# 2019SpaceAppsTrophy.net
KiCad netlist of a schematic drawn in EAGLE
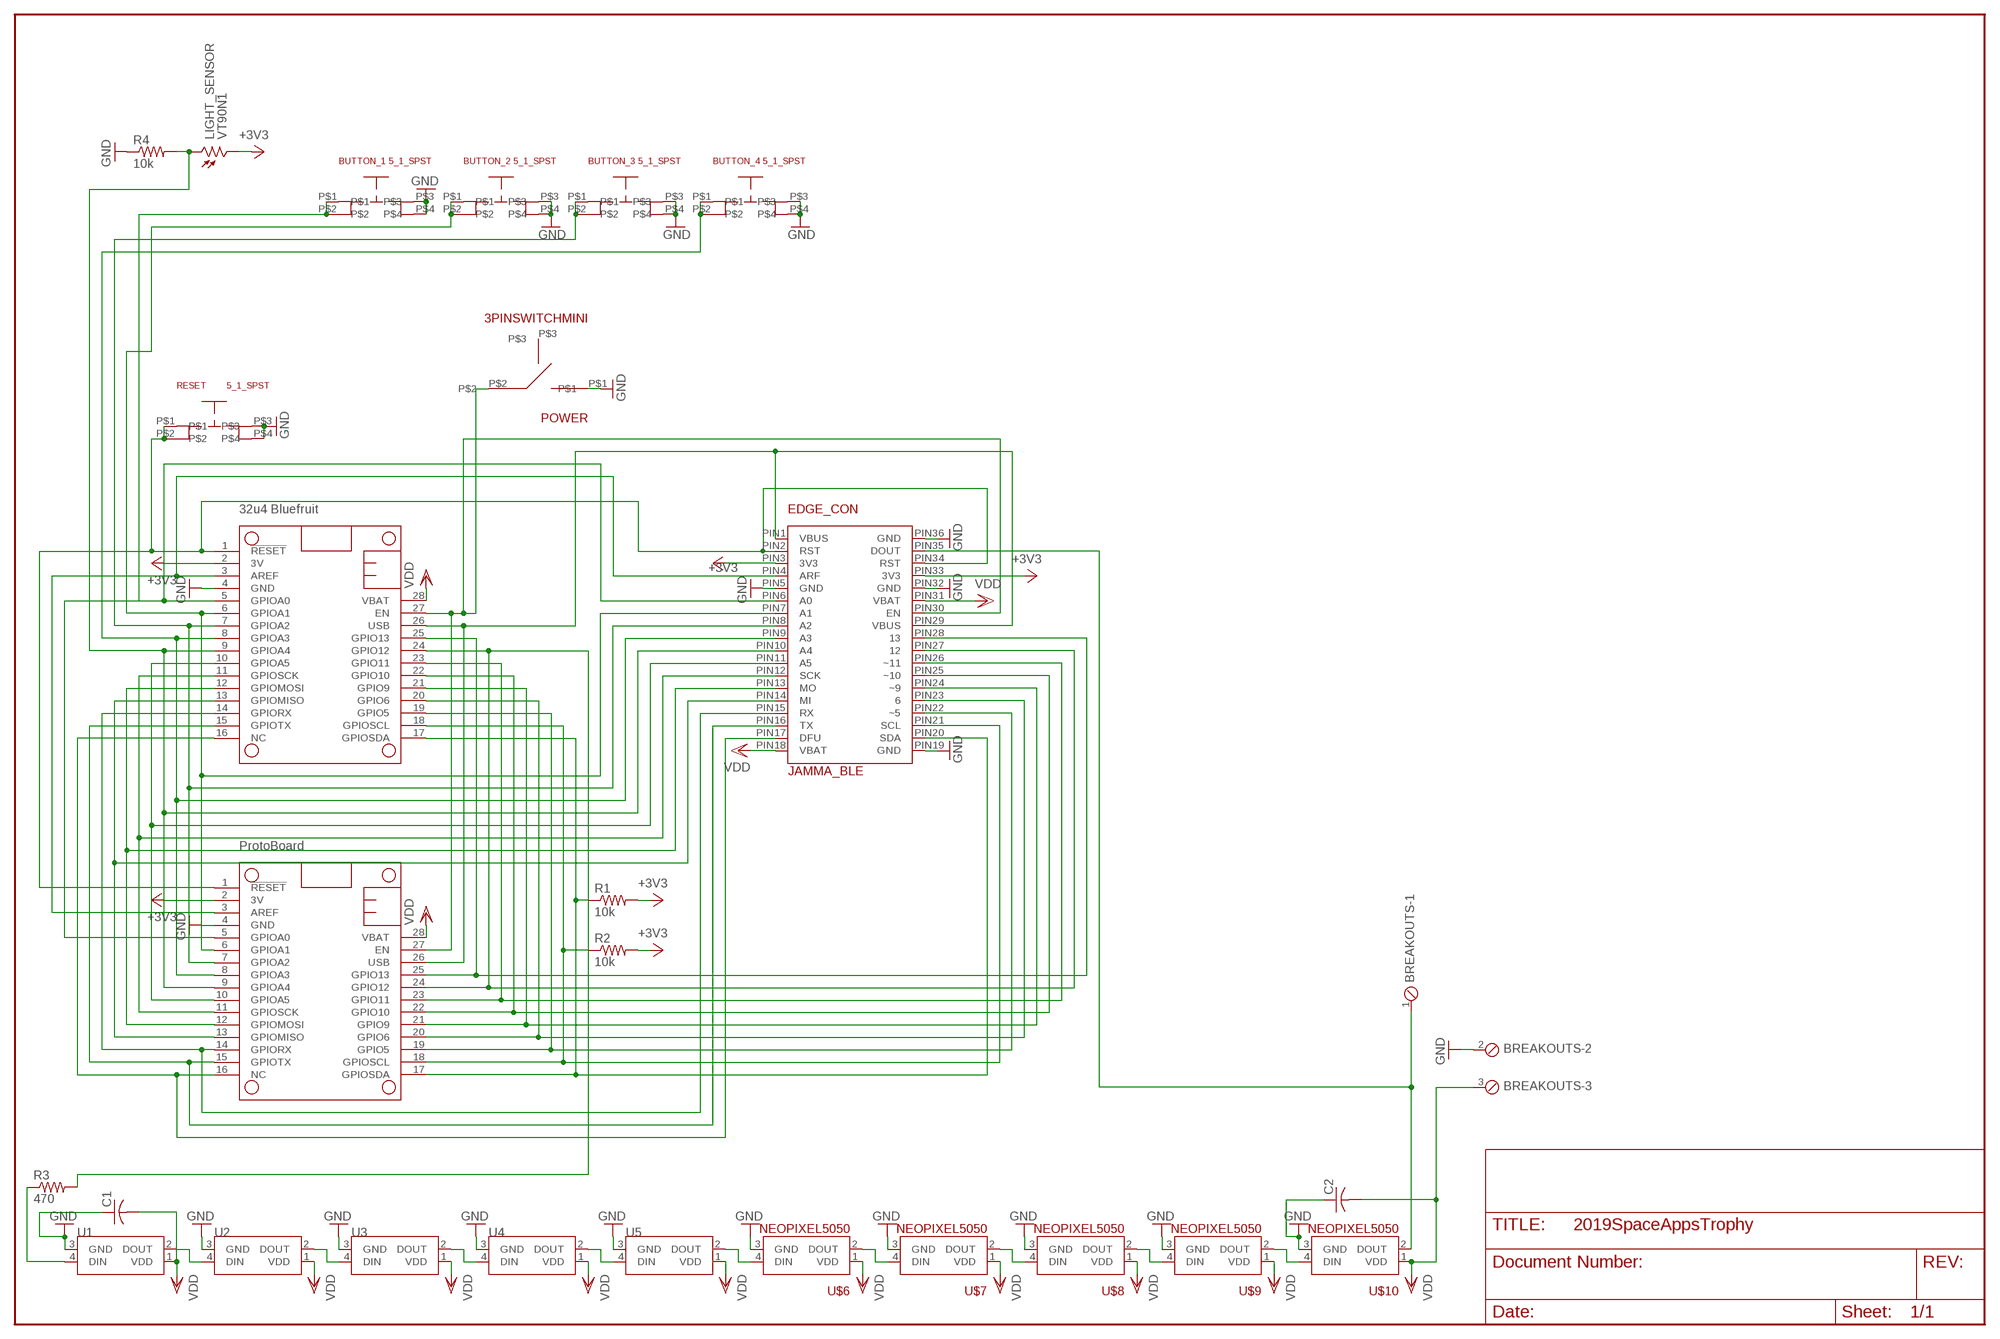
[diagram p0: schematic, sheet 1]

(export (version "E")
  (design (tool "Eeschema 10.0.6"))
  (components
    (comp (ref "BREAKOUTS")
      (value "MPT3")
      (footprint "eagle-import:3POL254")
      (libsource (lib "eagle-import") (part "MPT3"))
    )
    (comp (ref "BUTTON_1")
      (value "5_1_SPST")
      (footprint "eagle-import:5_1_SPST")
      (libsource (lib "eagle-import") (part "5_1_SPST"))
    )
    (comp (ref "BUTTON_2")
      (value "5_1_SPST")
      (footprint "eagle-import:5_1_SPST")
      (libsource (lib "eagle-import") (part "5_1_SPST"))
    )
    (comp (ref "BUTTON_3")
      (value "5_1_SPST")
      (footprint "eagle-import:5_1_SPST")
      (libsource (lib "eagle-import") (part "5_1_SPST"))
    )
    (comp (ref "BUTTON_4")
      (value "5_1_SPST")
      (footprint "eagle-import:5_1_SPST")
      (libsource (lib "eagle-import") (part "5_1_SPST"))
    )
    (comp (ref "C1")
      (value "C-USC0805")
      (footprint "eagle-import:C0805")
      (libsource (lib "eagle-import") (part "C-USC0805"))
    )
    (comp (ref "C2")
      (value "C-USC0805")
      (footprint "eagle-import:C0805")
      (libsource (lib "eagle-import") (part "C-USC0805"))
    )
    (comp (ref "EDGE_CON")
      (value "JAMMA_BLE")
      (footprint "eagle-import:JAMMA-28_56")
      (libsource (lib "eagle-import") (part "JAMMA_BLE"))
    )
    (comp (ref "LIGHT_SENSOR")
      (value "VT90N1")
      (footprint "eagle-import:VT900")
      (libsource (lib "eagle-import") (part "VT90N1"))
    )
    (comp (ref "MS2")
      (value "FEATHERWING")
      (footprint "eagle-import:FEATHERWING")
      (libsource (lib "eagle-import") (part "FEATHERWING"))
    )
    (comp (ref "POWER")
      (value "3PINSWITCHMINI")
      (footprint "eagle-import:3PINMINI")
      (libsource (lib "eagle-import") (part "3PINSWITCHMINI"))
    )
    (comp (ref "PROTOBOARD")
      (value "FEATHERWING")
      (footprint "eagle-import:FEATHERWING")
      (libsource (lib "eagle-import") (part "FEATHERWING"))
    )
    (comp (ref "R1")
      (value "10k")
      (footprint "eagle-import:M0805")
      (libsource (lib "eagle-import") (part "R-US_M0805"))
    )
    (comp (ref "R2")
      (value "10k")
      (footprint "eagle-import:M0805")
      (libsource (lib "eagle-import") (part "R-US_M0805"))
    )
    (comp (ref "R3")
      (value "470")
      (footprint "eagle-import:M0805")
      (libsource (lib "eagle-import") (part "R-US_M0805"))
    )
    (comp (ref "R4")
      (value "10k")
      (footprint "eagle-import:M0805")
      (libsource (lib "eagle-import") (part "R-US_M0805"))
    )
    (comp (ref "RESET")
      (value "5_1_SPST")
      (footprint "eagle-import:5_1_SPST")
      (libsource (lib "eagle-import") (part "5_1_SPST"))
    )
    (comp (ref "U$1")
      (value "NEOPIXEL5050")
      (footprint "eagle-import:NEOPIXEL5050")
      (libsource (lib "eagle-import") (part "NEOPIXEL5050"))
    )
    (comp (ref "U$2")
      (value "NEOPIXEL5050")
      (footprint "eagle-import:NEOPIXEL5050")
      (libsource (lib "eagle-import") (part "NEOPIXEL5050"))
    )
    (comp (ref "U$3")
      (value "NEOPIXEL5050")
      (footprint "eagle-import:NEOPIXEL5050")
      (libsource (lib "eagle-import") (part "NEOPIXEL5050"))
    )
    (comp (ref "U$4")
      (value "NEOPIXEL5050")
      (footprint "eagle-import:NEOPIXEL5050")
      (libsource (lib "eagle-import") (part "NEOPIXEL5050"))
    )
    (comp (ref "U$5")
      (value "NEOPIXEL5050")
      (footprint "eagle-import:NEOPIXEL5050")
      (libsource (lib "eagle-import") (part "NEOPIXEL5050"))
    )
    (comp (ref "U$6")
      (value "NEOPIXEL5050")
      (footprint "eagle-import:NEOPIXEL5050")
      (libsource (lib "eagle-import") (part "NEOPIXEL5050"))
    )
    (comp (ref "U$7")
      (value "NEOPIXEL5050")
      (footprint "eagle-import:NEOPIXEL5050")
      (libsource (lib "eagle-import") (part "NEOPIXEL5050"))
    )
    (comp (ref "U$8")
      (value "NEOPIXEL5050")
      (footprint "eagle-import:NEOPIXEL5050")
      (libsource (lib "eagle-import") (part "NEOPIXEL5050"))
    )
    (comp (ref "U$9")
      (value "NEOPIXEL5050")
      (footprint "eagle-import:NEOPIXEL5050")
      (libsource (lib "eagle-import") (part "NEOPIXEL5050"))
    )
    (comp (ref "U$10")
      (value "NEOPIXEL5050")
      (footprint "eagle-import:NEOPIXEL5050")
      (libsource (lib "eagle-import") (part "NEOPIXEL5050"))
    )
  )
  (nets
    (net (code "1") (name "+3V3") (class "Default")
      (node (ref "EDGE_CON") (pin "PIN3") (pinfunction "3V3_PIN3") (pintype "bidirectional"))
      (node (ref "EDGE_CON") (pin "PIN33") (pinfunction "3V3_PIN33") (pintype "bidirectional"))
      (node (ref "LIGHT_SENSOR") (pin "2") (pinfunction "2_2") (pintype "passive"))
      (node (ref "MS2") (pin "2") (pinfunction "3V_2") (pintype "power_in"))
      (node (ref "PROTOBOARD") (pin "2") (pinfunction "3V_2") (pintype "power_in"))
      (node (ref "R1") (pin "2") (pinfunction "2_2") (pintype "passive"))
      (node (ref "R2") (pin "2") (pinfunction "2_2") (pintype "passive"))
    )
    (net (code "2") (name "GND") (class "Default")
      (node (ref "BREAKOUTS") (pin "2") (pinfunction "1_2") (pintype "passive"))
      (node (ref "BUTTON_1") (pin "P$3") (pinfunction "P$3_P$3") (pintype "bidirectional"))
      (node (ref "BUTTON_1") (pin "P$4") (pinfunction "P$4_P$4") (pintype "bidirectional"))
      (node (ref "BUTTON_2") (pin "P$3") (pinfunction "P$3_P$3") (pintype "bidirectional"))
      (node (ref "BUTTON_2") (pin "P$4") (pinfunction "P$4_P$4") (pintype "bidirectional"))
      (node (ref "BUTTON_3") (pin "P$3") (pinfunction "P$3_P$3") (pintype "bidirectional"))
      (node (ref "BUTTON_3") (pin "P$4") (pinfunction "P$4_P$4") (pintype "bidirectional"))
      (node (ref "BUTTON_4") (pin "P$3") (pinfunction "P$3_P$3") (pintype "bidirectional"))
      (node (ref "BUTTON_4") (pin "P$4") (pinfunction "P$4_P$4") (pintype "bidirectional"))
      (node (ref "C1") (pin "1") (pinfunction "1_1") (pintype "passive"))
      (node (ref "C2") (pin "1") (pinfunction "1_1") (pintype "passive"))
      (node (ref "EDGE_CON") (pin "PIN19") (pinfunction "GND_PIN19") (pintype "bidirectional"))
      (node (ref "EDGE_CON") (pin "PIN32") (pinfunction "GND_PIN32") (pintype "bidirectional"))
      (node (ref "EDGE_CON") (pin "PIN36") (pinfunction "GND_PIN36") (pintype "bidirectional"))
      (node (ref "EDGE_CON") (pin "PIN5") (pinfunction "GND_PIN5") (pintype "bidirectional"))
      (node (ref "MS2") (pin "4") (pinfunction "GND_4") (pintype "power_in"))
      (node (ref "POWER") (pin "P$1") (pinfunction "P$1_P$1") (pintype "bidirectional"))
      (node (ref "PROTOBOARD") (pin "4") (pinfunction "GND_4") (pintype "power_in"))
      (node (ref "R4") (pin "1") (pinfunction "1_1") (pintype "passive"))
      (node (ref "RESET") (pin "P$3") (pinfunction "P$3_P$3") (pintype "bidirectional"))
      (node (ref "RESET") (pin "P$4") (pinfunction "P$4_P$4") (pintype "bidirectional"))
      (node (ref "U$1") (pin "3") (pinfunction "GND_3") (pintype "bidirectional"))
      (node (ref "U$10") (pin "3") (pinfunction "GND_3") (pintype "bidirectional"))
      (node (ref "U$2") (pin "3") (pinfunction "GND_3") (pintype "bidirectional"))
      (node (ref "U$3") (pin "3") (pinfunction "GND_3") (pintype "bidirectional"))
      (node (ref "U$4") (pin "3") (pinfunction "GND_3") (pintype "bidirectional"))
      (node (ref "U$5") (pin "3") (pinfunction "GND_3") (pintype "bidirectional"))
      (node (ref "U$6") (pin "3") (pinfunction "GND_3") (pintype "bidirectional"))
      (node (ref "U$7") (pin "3") (pinfunction "GND_3") (pintype "bidirectional"))
      (node (ref "U$8") (pin "3") (pinfunction "GND_3") (pintype "bidirectional"))
      (node (ref "U$9") (pin "3") (pinfunction "GND_3") (pintype "bidirectional"))
    )
    (net (code "3") (name "Net-(EDGE_CON-6)") (class "Default")
      (node (ref "EDGE_CON") (pin "PIN23") (pinfunction "6_PIN23") (pintype "bidirectional"))
      (node (ref "MS2") (pin "20") (pinfunction "GPIO6_20") (pintype "bidirectional"))
      (node (ref "PROTOBOARD") (pin "20") (pinfunction "GPIO6_20") (pintype "bidirectional"))
    )
    (net (code "4") (name "Net-(EDGE_CON-12)") (class "Default")
      (node (ref "EDGE_CON") (pin "PIN27") (pinfunction "12_PIN27") (pintype "bidirectional"))
      (node (ref "MS2") (pin "24") (pinfunction "GPIO12_24") (pintype "bidirectional"))
      (node (ref "PROTOBOARD") (pin "24") (pinfunction "GPIO12_24") (pintype "bidirectional"))
      (node (ref "R3") (pin "2") (pinfunction "2_2") (pintype "passive"))
    )
    (net (code "5") (name "Net-(EDGE_CON-13)") (class "Default")
      (node (ref "EDGE_CON") (pin "PIN28") (pinfunction "13_PIN28") (pintype "bidirectional"))
      (node (ref "MS2") (pin "25") (pinfunction "GPIO13_25") (pintype "bidirectional"))
      (node (ref "PROTOBOARD") (pin "25") (pinfunction "GPIO13_25") (pintype "bidirectional"))
    )
    (net (code "6") (name "Net-(EDGE_CON-A0)") (class "Default")
      (node (ref "BUTTON_1") (pin "P$1") (pinfunction "P$1_P$1") (pintype "bidirectional"))
      (node (ref "BUTTON_1") (pin "P$2") (pinfunction "P$2_P$2") (pintype "bidirectional"))
      (node (ref "EDGE_CON") (pin "PIN6") (pinfunction "A0_PIN6") (pintype "bidirectional"))
      (node (ref "MS2") (pin "5") (pinfunction "GPIOA0_5") (pintype "bidirectional"))
      (node (ref "PROTOBOARD") (pin "5") (pinfunction "GPIOA0_5") (pintype "bidirectional"))
    )
    (net (code "7") (name "Net-(EDGE_CON-A1)") (class "Default")
      (node (ref "BUTTON_2") (pin "P$1") (pinfunction "P$1_P$1") (pintype "bidirectional"))
      (node (ref "BUTTON_2") (pin "P$2") (pinfunction "P$2_P$2") (pintype "bidirectional"))
      (node (ref "EDGE_CON") (pin "PIN7") (pinfunction "A1_PIN7") (pintype "bidirectional"))
      (node (ref "MS2") (pin "6") (pinfunction "GPIOA1_6") (pintype "bidirectional"))
      (node (ref "PROTOBOARD") (pin "6") (pinfunction "GPIOA1_6") (pintype "bidirectional"))
    )
    (net (code "8") (name "Net-(EDGE_CON-A2)") (class "Default")
      (node (ref "BUTTON_3") (pin "P$1") (pinfunction "P$1_P$1") (pintype "bidirectional"))
      (node (ref "BUTTON_3") (pin "P$2") (pinfunction "P$2_P$2") (pintype "bidirectional"))
      (node (ref "EDGE_CON") (pin "PIN8") (pinfunction "A2_PIN8") (pintype "bidirectional"))
      (node (ref "MS2") (pin "7") (pinfunction "GPIOA2_7") (pintype "bidirectional"))
      (node (ref "PROTOBOARD") (pin "7") (pinfunction "GPIOA2_7") (pintype "bidirectional"))
    )
    (net (code "9") (name "Net-(EDGE_CON-A3)") (class "Default")
      (node (ref "BUTTON_4") (pin "P$1") (pinfunction "P$1_P$1") (pintype "bidirectional"))
      (node (ref "BUTTON_4") (pin "P$2") (pinfunction "P$2_P$2") (pintype "bidirectional"))
      (node (ref "EDGE_CON") (pin "PIN9") (pinfunction "A3_PIN9") (pintype "bidirectional"))
      (node (ref "MS2") (pin "8") (pinfunction "GPIOA3_8") (pintype "bidirectional"))
      (node (ref "PROTOBOARD") (pin "8") (pinfunction "GPIOA3_8") (pintype "bidirectional"))
    )
    (net (code "10") (name "Net-(EDGE_CON-A4)") (class "Default")
      (node (ref "EDGE_CON") (pin "PIN10") (pinfunction "A4_PIN10") (pintype "bidirectional"))
      (node (ref "LIGHT_SENSOR") (pin "1") (pinfunction "1_1") (pintype "passive"))
      (node (ref "MS2") (pin "9") (pinfunction "GPIOA4_9") (pintype "bidirectional"))
      (node (ref "PROTOBOARD") (pin "9") (pinfunction "GPIOA4_9") (pintype "bidirectional"))
      (node (ref "R4") (pin "2") (pinfunction "2_2") (pintype "passive"))
    )
    (net (code "11") (name "Net-(EDGE_CON-A5)") (class "Default")
      (node (ref "EDGE_CON") (pin "PIN11") (pinfunction "A5_PIN11") (pintype "bidirectional"))
      (node (ref "MS2") (pin "10") (pinfunction "GPIOA5_10") (pintype "bidirectional"))
      (node (ref "PROTOBOARD") (pin "10") (pinfunction "GPIOA5_10") (pintype "bidirectional"))
    )
    (net (code "12") (name "Net-(EDGE_CON-ARF)") (class "Default")
      (node (ref "EDGE_CON") (pin "PIN4") (pinfunction "ARF_PIN4") (pintype "bidirectional"))
      (node (ref "MS2") (pin "3") (pinfunction "AREF_3") (pintype "passive"))
      (node (ref "PROTOBOARD") (pin "3") (pinfunction "AREF_3") (pintype "passive"))
    )
    (net (code "13") (name "Net-(EDGE_CON-DFU)") (class "Default")
      (node (ref "EDGE_CON") (pin "PIN17") (pinfunction "DFU_PIN17") (pintype "bidirectional"))
      (node (ref "MS2") (pin "16") (pinfunction "NC_16") (pintype "passive"))
      (node (ref "PROTOBOARD") (pin "16") (pinfunction "NC_16") (pintype "passive"))
    )
    (net (code "14") (name "Net-(EDGE_CON-DOUT)") (class "Default")
      (node (ref "BREAKOUTS") (pin "1") (pinfunction "1_1") (pintype "passive"))
      (node (ref "EDGE_CON") (pin "PIN35") (pinfunction "DOUT_PIN35") (pintype "bidirectional"))
      (node (ref "U$10") (pin "2") (pinfunction "DOUT_2") (pintype "bidirectional"))
    )
    (net (code "15") (name "Net-(EDGE_CON-EN)") (class "Default")
      (node (ref "EDGE_CON") (pin "PIN30") (pinfunction "EN_PIN30") (pintype "bidirectional"))
      (node (ref "MS2") (pin "27") (pinfunction "EN_27") (pintype "passive"))
      (node (ref "POWER") (pin "P$2") (pinfunction "P$2_P$2") (pintype "bidirectional"))
      (node (ref "PROTOBOARD") (pin "27") (pinfunction "EN_27") (pintype "passive"))
    )
    (net (code "16") (name "Net-(EDGE_CON-MI)") (class "Default")
      (node (ref "EDGE_CON") (pin "PIN14") (pinfunction "MI_PIN14") (pintype "bidirectional"))
      (node (ref "MS2") (pin "13") (pinfunction "GPIOMISO_13") (pintype "bidirectional"))
      (node (ref "PROTOBOARD") (pin "13") (pinfunction "GPIOMISO_13") (pintype "bidirectional"))
    )
    (net (code "17") (name "Net-(EDGE_CON-MO)") (class "Default")
      (node (ref "EDGE_CON") (pin "PIN13") (pinfunction "MO_PIN13") (pintype "bidirectional"))
      (node (ref "MS2") (pin "12") (pinfunction "GPIOMOSI_12") (pintype "bidirectional"))
      (node (ref "PROTOBOARD") (pin "12") (pinfunction "GPIOMOSI_12") (pintype "bidirectional"))
    )
    (net (code "18") (name "Net-(EDGE_CON-RX)") (class "Default")
      (node (ref "EDGE_CON") (pin "PIN15") (pinfunction "RX_PIN15") (pintype "bidirectional"))
      (node (ref "MS2") (pin "14") (pinfunction "GPIORX_14") (pintype "bidirectional"))
      (node (ref "PROTOBOARD") (pin "14") (pinfunction "GPIORX_14") (pintype "bidirectional"))
    )
    (net (code "19") (name "Net-(EDGE_CON-SCK)") (class "Default")
      (node (ref "EDGE_CON") (pin "PIN12") (pinfunction "SCK_PIN12") (pintype "bidirectional"))
      (node (ref "MS2") (pin "11") (pinfunction "GPIOSCK_11") (pintype "bidirectional"))
      (node (ref "PROTOBOARD") (pin "11") (pinfunction "GPIOSCK_11") (pintype "bidirectional"))
    )
    (net (code "20") (name "Net-(EDGE_CON-SCL)") (class "Default")
      (node (ref "EDGE_CON") (pin "PIN21") (pinfunction "SCL_PIN21") (pintype "bidirectional"))
      (node (ref "MS2") (pin "18") (pinfunction "GPIOSCL_18") (pintype "bidirectional"))
      (node (ref "PROTOBOARD") (pin "18") (pinfunction "GPIOSCL_18") (pintype "bidirectional"))
      (node (ref "R2") (pin "1") (pinfunction "1_1") (pintype "passive"))
    )
    (net (code "21") (name "Net-(EDGE_CON-SDA)") (class "Default")
      (node (ref "EDGE_CON") (pin "PIN20") (pinfunction "SDA_PIN20") (pintype "bidirectional"))
      (node (ref "MS2") (pin "17") (pinfunction "GPIOSDA_17") (pintype "bidirectional"))
      (node (ref "PROTOBOARD") (pin "17") (pinfunction "GPIOSDA_17") (pintype "bidirectional"))
      (node (ref "R1") (pin "1") (pinfunction "1_1") (pintype "passive"))
    )
    (net (code "22") (name "Net-(EDGE_CON-TX)") (class "Default")
      (node (ref "EDGE_CON") (pin "PIN16") (pinfunction "TX_PIN16") (pintype "bidirectional"))
      (node (ref "MS2") (pin "15") (pinfunction "GPIOTX_15") (pintype "bidirectional"))
      (node (ref "PROTOBOARD") (pin "15") (pinfunction "GPIOTX_15") (pintype "bidirectional"))
    )
    (net (code "23") (name "Net-(EDGE_CON-~{5})") (class "Default")
      (node (ref "EDGE_CON") (pin "PIN22") (pinfunction "~{5}_PIN22") (pintype "bidirectional"))
      (node (ref "MS2") (pin "19") (pinfunction "GPIO5_19") (pintype "bidirectional"))
      (node (ref "PROTOBOARD") (pin "19") (pinfunction "GPIO5_19") (pintype "bidirectional"))
    )
    (net (code "24") (name "Net-(EDGE_CON-~{9})") (class "Default")
      (node (ref "EDGE_CON") (pin "PIN24") (pinfunction "~{9}_PIN24") (pintype "bidirectional"))
      (node (ref "MS2") (pin "21") (pinfunction "GPIO9_21") (pintype "bidirectional"))
      (node (ref "PROTOBOARD") (pin "21") (pinfunction "GPIO9_21") (pintype "bidirectional"))
    )
    (net (code "25") (name "Net-(EDGE_CON-~{10})") (class "Default")
      (node (ref "EDGE_CON") (pin "PIN25") (pinfunction "~{10}_PIN25") (pintype "bidirectional"))
      (node (ref "MS2") (pin "22") (pinfunction "GPIO10_22") (pintype "bidirectional"))
      (node (ref "PROTOBOARD") (pin "22") (pinfunction "GPIO10_22") (pintype "bidirectional"))
    )
    (net (code "26") (name "Net-(EDGE_CON-~{11})") (class "Default")
      (node (ref "EDGE_CON") (pin "PIN26") (pinfunction "~{11}_PIN26") (pintype "bidirectional"))
      (node (ref "MS2") (pin "23") (pinfunction "GPIO11_23") (pintype "bidirectional"))
      (node (ref "PROTOBOARD") (pin "23") (pinfunction "GPIO11_23") (pintype "bidirectional"))
    )
    (net (code "27") (name "Net-(MS2-USB)") (class "Default")
      (node (ref "EDGE_CON") (pin "PIN1") (pinfunction "VBUS_PIN1") (pintype "bidirectional"))
      (node (ref "EDGE_CON") (pin "PIN29") (pinfunction "VBUS_PIN29") (pintype "bidirectional"))
      (node (ref "MS2") (pin "26") (pinfunction "USB_26") (pintype "power_in"))
      (node (ref "PROTOBOARD") (pin "26") (pinfunction "USB_26") (pintype "power_in"))
    )
    (net (code "28") (name "Net-(MS2-~{RESET})") (class "Default")
      (node (ref "EDGE_CON") (pin "PIN2") (pinfunction "RST_PIN2") (pintype "bidirectional"))
      (node (ref "EDGE_CON") (pin "PIN34") (pinfunction "RST_PIN34") (pintype "bidirectional"))
      (node (ref "MS2") (pin "1") (pinfunction "~{RESET}_1") (pintype "input"))
      (node (ref "PROTOBOARD") (pin "1") (pinfunction "~{RESET}_1") (pintype "input"))
      (node (ref "RESET") (pin "P$1") (pinfunction "P$1_P$1") (pintype "bidirectional"))
      (node (ref "RESET") (pin "P$2") (pinfunction "P$2_P$2") (pintype "bidirectional"))
    )
    (net (code "29") (name "Net-(U$1-DIN)") (class "Default")
      (node (ref "R3") (pin "1") (pinfunction "1_1") (pintype "passive"))
      (node (ref "U$1") (pin "4") (pinfunction "DIN_4") (pintype "bidirectional"))
    )
    (net (code "30") (name "Net-(U$1-DOUT)") (class "Default")
      (node (ref "U$1") (pin "2") (pinfunction "DOUT_2") (pintype "bidirectional"))
      (node (ref "U$2") (pin "4") (pinfunction "DIN_4") (pintype "bidirectional"))
    )
    (net (code "31") (name "Net-(U$2-DOUT)") (class "Default")
      (node (ref "U$2") (pin "2") (pinfunction "DOUT_2") (pintype "bidirectional"))
      (node (ref "U$3") (pin "4") (pinfunction "DIN_4") (pintype "bidirectional"))
    )
    (net (code "32") (name "Net-(U$3-DOUT)") (class "Default")
      (node (ref "U$3") (pin "2") (pinfunction "DOUT_2") (pintype "bidirectional"))
      (node (ref "U$4") (pin "4") (pinfunction "DIN_4") (pintype "bidirectional"))
    )
    (net (code "33") (name "Net-(U$4-DOUT)") (class "Default")
      (node (ref "U$4") (pin "2") (pinfunction "DOUT_2") (pintype "bidirectional"))
      (node (ref "U$5") (pin "4") (pinfunction "DIN_4") (pintype "bidirectional"))
    )
    (net (code "34") (name "Net-(U$5-DOUT)") (class "Default")
      (node (ref "U$5") (pin "2") (pinfunction "DOUT_2") (pintype "bidirectional"))
      (node (ref "U$6") (pin "4") (pinfunction "DIN_4") (pintype "bidirectional"))
    )
    (net (code "35") (name "Net-(U$6-DOUT)") (class "Default")
      (node (ref "U$6") (pin "2") (pinfunction "DOUT_2") (pintype "bidirectional"))
      (node (ref "U$7") (pin "4") (pinfunction "DIN_4") (pintype "bidirectional"))
    )
    (net (code "36") (name "Net-(U$7-DOUT)") (class "Default")
      (node (ref "U$7") (pin "2") (pinfunction "DOUT_2") (pintype "bidirectional"))
      (node (ref "U$8") (pin "4") (pinfunction "DIN_4") (pintype "bidirectional"))
    )
    (net (code "37") (name "Net-(U$8-DOUT)") (class "Default")
      (node (ref "U$8") (pin "2") (pinfunction "DOUT_2") (pintype "bidirectional"))
      (node (ref "U$9") (pin "4") (pinfunction "DIN_4") (pintype "bidirectional"))
    )
    (net (code "38") (name "Net-(U$10-DIN)") (class "Default")
      (node (ref "U$10") (pin "4") (pinfunction "DIN_4") (pintype "bidirectional"))
      (node (ref "U$9") (pin "2") (pinfunction "DOUT_2") (pintype "bidirectional"))
    )
    (net (code "39") (name "VDD") (class "Default")
      (node (ref "BREAKOUTS") (pin "3") (pinfunction "1_3") (pintype "passive"))
      (node (ref "C1") (pin "2") (pinfunction "2_2") (pintype "passive"))
      (node (ref "C2") (pin "2") (pinfunction "2_2") (pintype "passive"))
      (node (ref "EDGE_CON") (pin "PIN18") (pinfunction "VBAT_PIN18") (pintype "bidirectional"))
      (node (ref "EDGE_CON") (pin "PIN31") (pinfunction "VBAT_PIN31") (pintype "bidirectional"))
      (node (ref "MS2") (pin "28") (pinfunction "VBAT_28") (pintype "power_in"))
      (node (ref "PROTOBOARD") (pin "28") (pinfunction "VBAT_28") (pintype "power_in"))
      (node (ref "U$1") (pin "1") (pinfunction "VDD_1") (pintype "bidirectional"))
      (node (ref "U$10") (pin "1") (pinfunction "VDD_1") (pintype "bidirectional"))
      (node (ref "U$2") (pin "1") (pinfunction "VDD_1") (pintype "bidirectional"))
      (node (ref "U$3") (pin "1") (pinfunction "VDD_1") (pintype "bidirectional"))
      (node (ref "U$4") (pin "1") (pinfunction "VDD_1") (pintype "bidirectional"))
      (node (ref "U$5") (pin "1") (pinfunction "VDD_1") (pintype "bidirectional"))
      (node (ref "U$6") (pin "1") (pinfunction "VDD_1") (pintype "bidirectional"))
      (node (ref "U$7") (pin "1") (pinfunction "VDD_1") (pintype "bidirectional"))
      (node (ref "U$8") (pin "1") (pinfunction "VDD_1") (pintype "bidirectional"))
      (node (ref "U$9") (pin "1") (pinfunction "VDD_1") (pintype "bidirectional"))
    )
    (net (code "40") (name "unconnected-(POWER-PadP$3)") (class "Default")
      (node (ref "POWER") (pin "P$3") (pinfunction "P$3_P$3") (pintype "bidirectional"))
    )
  )
)
